# 07_ux.net
KiCad netlist of a schematic drawn in Altium Designer
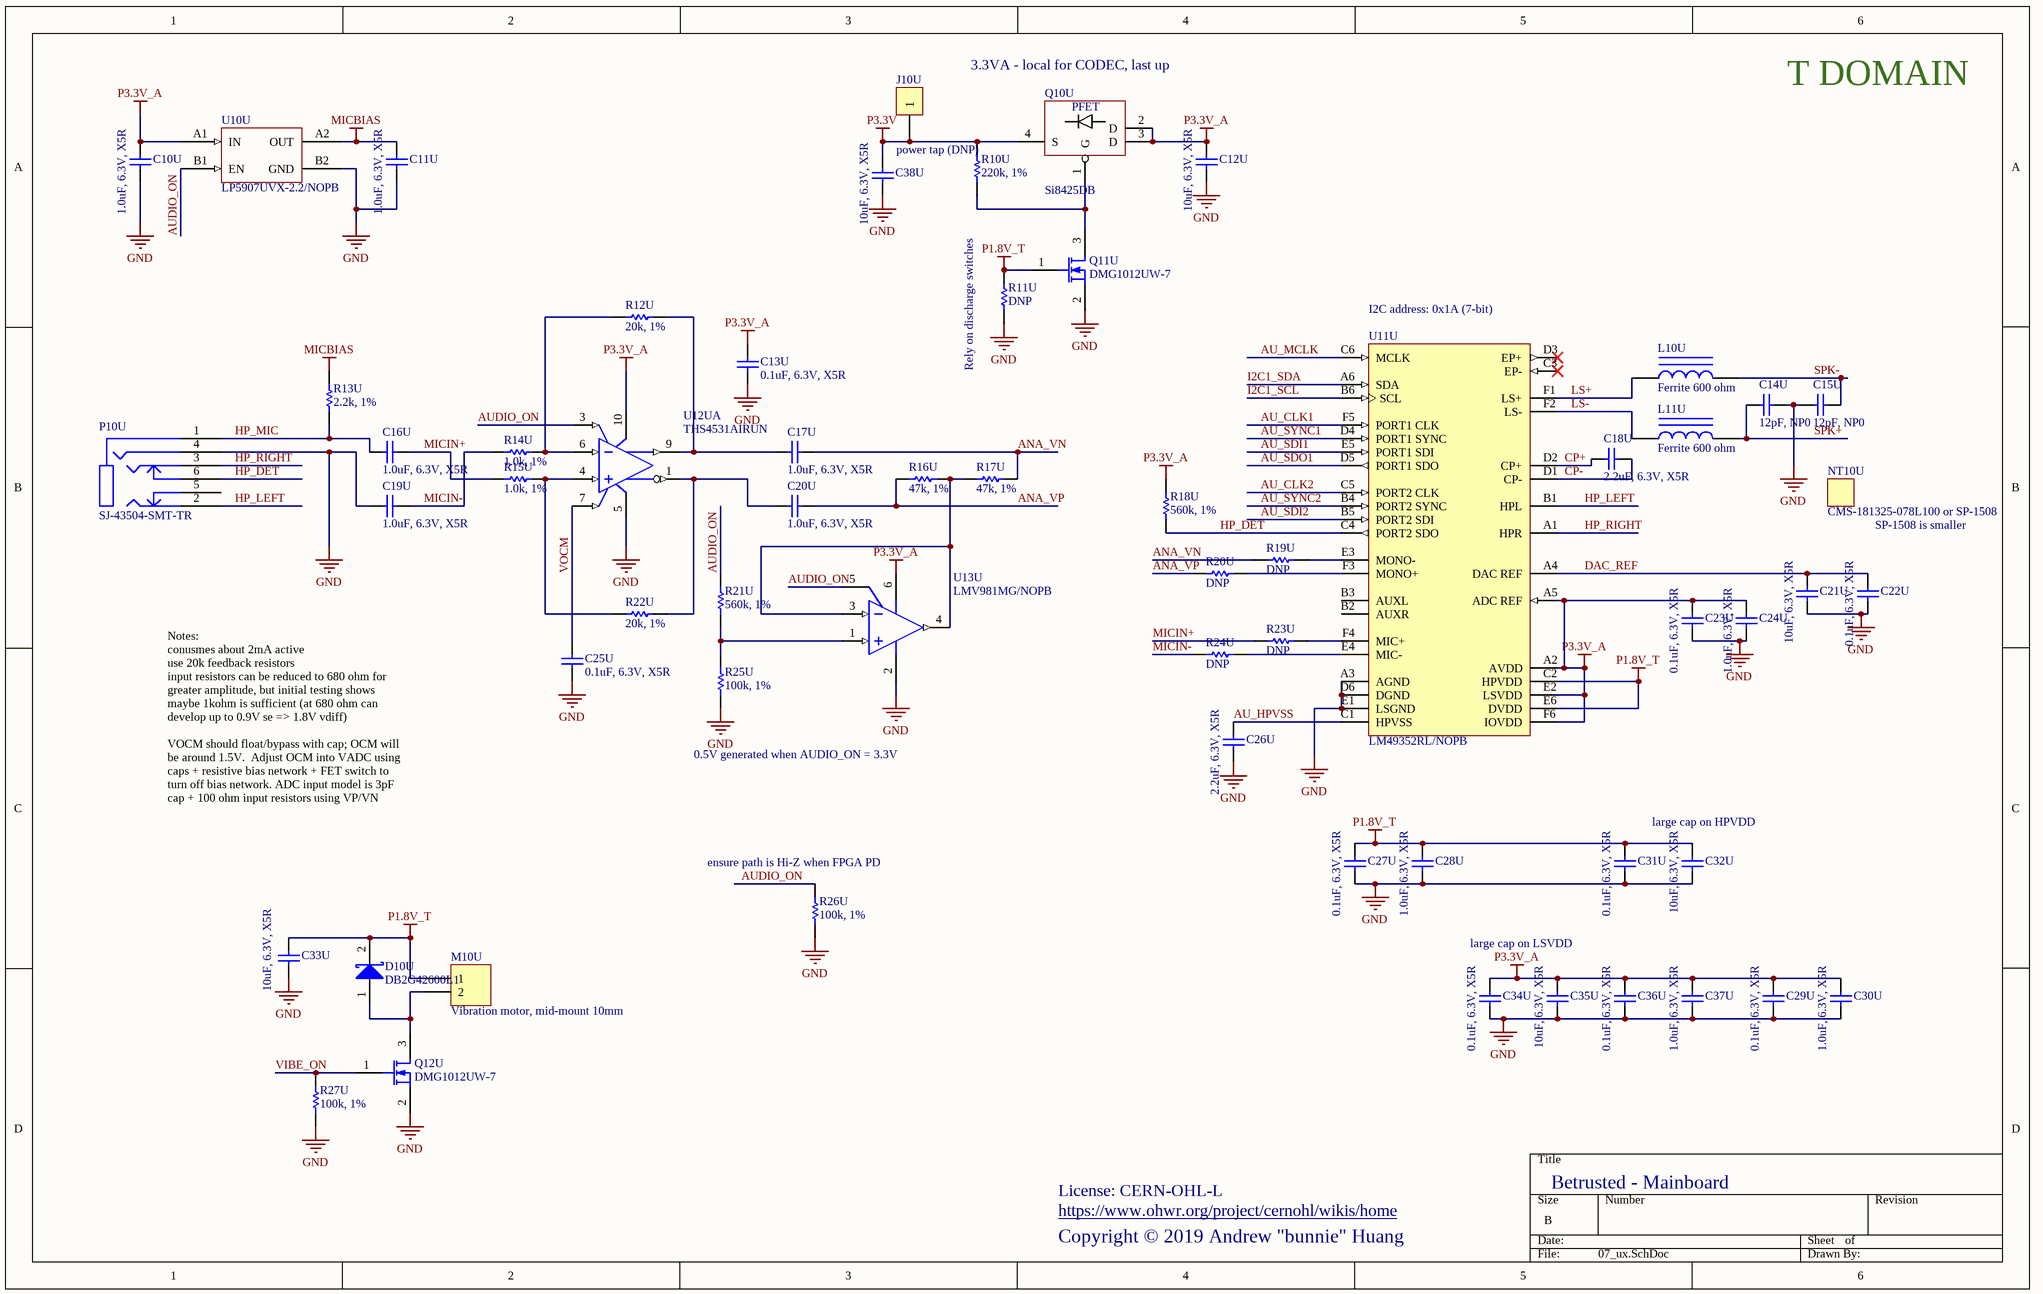
[diagram p0: 07_ux.SchDoc]

(export (version "E")
  (design (tool "Eeschema 10.0.6"))
  (components
    (comp (ref "C10U")
      (value "1.0uF, 6.3V, X5R")
      (footprint "B_CAP0201")
      (description "Capacitor (Semiconductor SIM Model)")
      (fields (field (name "MPN") "GRM033R60J105MEA2D"))
      (libsource (lib "Miscellaneous Devices") (part "Cap Semi"))
    )
    (comp (ref "C11U")
      (value "1.0uF, 6.3V, X5R")
      (footprint "B_CAP0201")
      (description "Capacitor (Semiconductor SIM Model)")
      (fields (field (name "MPN") "GRM033R60J105MEA2D"))
      (libsource (lib "Miscellaneous Devices") (part "Cap Semi"))
    )
    (comp (ref "C12U")
      (value "10uF, 6.3V, X5R")
      (footprint "B_CAP0603")
      (description "Capacitor (Semiconductor SIM Model)")
      (fields (field (name "MPN") "CL10A106MQ8NNNC"))
      (libsource (lib "Miscellaneous Devices") (part "Cap Semi"))
    )
    (comp (ref "C13U")
      (value "0.1uF, 6.3V, X5R")
      (footprint "B_CAP0201")
      (description "Capacitor (Semiconductor SIM Model)")
      (fields (field (name "MPN") "CL03A104KQ3NNNC"))
      (libsource (lib "Miscellaneous Devices") (part "Cap Semi"))
    )
    (comp (ref "C14U")
      (value "12pF, NP0")
      (footprint "B_CAP0201")
      (description "Capacitor (Semiconductor SIM Model)")
      (fields (field (name "MPN") "GRM0335C1E120JA01D"))
      (libsource (lib "Miscellaneous Devices") (part "Cap Semi"))
    )
    (comp (ref "C15U")
      (value "12pF, NP0")
      (footprint "B_CAP0201")
      (description "Capacitor (Semiconductor SIM Model)")
      (fields (field (name "MPN") "GRM0335C1E120JA01D"))
      (libsource (lib "Miscellaneous Devices") (part "Cap Semi"))
    )
    (comp (ref "C16U")
      (value "1.0uF, 6.3V, X5R")
      (footprint "B_CAP0201")
      (description "Capacitor (Semiconductor SIM Model)")
      (fields (field (name "MPN") "GRM033R60J105MEA2D"))
      (libsource (lib "Miscellaneous Devices") (part "Cap Semi"))
    )
    (comp (ref "C17U")
      (value "1.0uF, 6.3V, X5R")
      (footprint "B_CAP0201")
      (description "Capacitor (Semiconductor SIM Model)")
      (fields (field (name "MPN") "GRM033R60J105MEA2D"))
      (libsource (lib "Miscellaneous Devices") (part "Cap Semi"))
    )
    (comp (ref "C18U")
      (value "2.2uF, 6.3V, X5R")
      (footprint "B_CAP0402")
      (description "Capacitor (Semiconductor SIM Model)")
      (fields (field (name "MPN") "CL05A225MQ5NNNC"))
      (libsource (lib "Miscellaneous Devices") (part "Cap Semi"))
    )
    (comp (ref "C19U")
      (value "1.0uF, 6.3V, X5R")
      (footprint "B_CAP0201")
      (description "Capacitor (Semiconductor SIM Model)")
      (fields (field (name "MPN") "GRM033R60J105MEA2D"))
      (libsource (lib "Miscellaneous Devices") (part "Cap Semi"))
    )
    (comp (ref "C20U")
      (value "1.0uF, 6.3V, X5R")
      (footprint "B_CAP0201")
      (description "Capacitor (Semiconductor SIM Model)")
      (fields (field (name "MPN") "GRM033R60J105MEA2D"))
      (libsource (lib "Miscellaneous Devices") (part "Cap Semi"))
    )
    (comp (ref "C21U")
      (value "10uF, 6.3V, X5R")
      (footprint "B_CAP0603")
      (description "Capacitor (Semiconductor SIM Model)")
      (fields (field (name "MPN") "CL10A106MQ8NNNC"))
      (libsource (lib "Miscellaneous Devices") (part "Cap Semi"))
    )
    (comp (ref "C22U")
      (value "0.1uF, 6.3V, X5R")
      (footprint "B_CAP0201")
      (description "Capacitor (Semiconductor SIM Model)")
      (fields (field (name "MPN") "CL03A104KQ3NNNC"))
      (libsource (lib "Miscellaneous Devices") (part "Cap Semi"))
    )
    (comp (ref "C23U")
      (value "0.1uF, 6.3V, X5R")
      (footprint "B_CAP0201")
      (description "Capacitor (Semiconductor SIM Model)")
      (fields (field (name "MPN") "CL03A104KQ3NNNC"))
      (libsource (lib "Miscellaneous Devices") (part "Cap Semi"))
    )
    (comp (ref "C24U")
      (value "1.0uF, 6.3V, X5R")
      (footprint "B_CAP0201")
      (description "Capacitor (Semiconductor SIM Model)")
      (fields (field (name "MPN") "GRM033R60J105MEA2D"))
      (libsource (lib "Miscellaneous Devices") (part "Cap Semi"))
    )
    (comp (ref "C25U")
      (value "0.1uF, 6.3V, X5R")
      (footprint "B_CAP0201")
      (description "Capacitor (Semiconductor SIM Model)")
      (fields (field (name "MPN") "CL03A104KQ3NNNC"))
      (libsource (lib "Miscellaneous Devices") (part "Cap Semi"))
    )
    (comp (ref "C26U")
      (value "2.2uF, 6.3V, X5R")
      (footprint "B_CAP0402")
      (description "Capacitor (Semiconductor SIM Model)")
      (fields (field (name "MPN") "CL05A225MQ5NNNC"))
      (libsource (lib "Miscellaneous Devices") (part "Cap Semi"))
    )
    (comp (ref "C27U")
      (value "0.1uF, 6.3V, X5R")
      (footprint "B_CAP0201")
      (description "Capacitor (Semiconductor SIM Model)")
      (fields (field (name "MPN") "CL03A104KQ3NNNC"))
      (libsource (lib "Miscellaneous Devices") (part "Cap Semi"))
    )
    (comp (ref "C28U")
      (value "1.0uF, 6.3V, X5R")
      (footprint "B_CAP0201")
      (description "Capacitor (Semiconductor SIM Model)")
      (fields (field (name "MPN") "GRM033R60J105MEA2D"))
      (libsource (lib "Miscellaneous Devices") (part "Cap Semi"))
    )
    (comp (ref "C29U")
      (value "0.1uF, 6.3V, X5R")
      (footprint "B_CAP0201")
      (description "Capacitor (Semiconductor SIM Model)")
      (fields (field (name "MPN") "CL03A104KQ3NNNC"))
      (libsource (lib "Miscellaneous Devices") (part "Cap Semi"))
    )
    (comp (ref "C30U")
      (value "1.0uF, 6.3V, X5R")
      (footprint "B_CAP0201")
      (description "Capacitor (Semiconductor SIM Model)")
      (fields (field (name "MPN") "GRM033R60J105MEA2D"))
      (libsource (lib "Miscellaneous Devices") (part "Cap Semi"))
    )
    (comp (ref "C31U")
      (value "0.1uF, 6.3V, X5R")
      (footprint "B_CAP0201")
      (description "Capacitor (Semiconductor SIM Model)")
      (fields (field (name "MPN") "CL03A104KQ3NNNC"))
      (libsource (lib "Miscellaneous Devices") (part "Cap Semi"))
    )
    (comp (ref "C32U")
      (value "10uF, 6.3V, X5R")
      (footprint "B_CAP0603")
      (description "Capacitor (Semiconductor SIM Model)")
      (fields (field (name "MPN") "CL10A106MQ8NNNC"))
      (libsource (lib "Miscellaneous Devices") (part "Cap Semi"))
    )
    (comp (ref "C33U")
      (value "10uF, 6.3V, X5R")
      (footprint "B_CAP0603")
      (description "Capacitor (Semiconductor SIM Model)")
      (fields (field (name "MPN") "CL10A106MQ8NNNC"))
      (libsource (lib "Miscellaneous Devices") (part "Cap Semi"))
    )
    (comp (ref "C34U")
      (value "0.1uF, 6.3V, X5R")
      (footprint "B_CAP0201")
      (description "Capacitor (Semiconductor SIM Model)")
      (fields (field (name "MPN") "CL03A104KQ3NNNC"))
      (libsource (lib "Miscellaneous Devices") (part "Cap Semi"))
    )
    (comp (ref "C35U")
      (value "10uF, 6.3V, X5R")
      (footprint "B_CAP0603")
      (description "Capacitor (Semiconductor SIM Model)")
      (fields (field (name "MPN") "CL10A106MQ8NNNC"))
      (libsource (lib "Miscellaneous Devices") (part "Cap Semi"))
    )
    (comp (ref "C36U")
      (value "0.1uF, 6.3V, X5R")
      (footprint "B_CAP0201")
      (description "Capacitor (Semiconductor SIM Model)")
      (fields (field (name "MPN") "CL03A104KQ3NNNC"))
      (libsource (lib "Miscellaneous Devices") (part "Cap Semi"))
    )
    (comp (ref "C37U")
      (value "1.0uF, 6.3V, X5R")
      (footprint "B_CAP0201")
      (description "Capacitor (Semiconductor SIM Model)")
      (fields (field (name "MPN") "GRM033R60J105MEA2D"))
      (libsource (lib "Miscellaneous Devices") (part "Cap Semi"))
    )
    (comp (ref "C38U")
      (value "10uF, 6.3V, X5R")
      (footprint "B_CAP0603")
      (description "Capacitor (Semiconductor SIM Model)")
      (fields (field (name "MPN") "CL10A106MQ8NNNC"))
      (libsource (lib "Miscellaneous Devices") (part "Cap Semi"))
    )
    (comp (ref "D10U")
      (value "DB2G42600L1")
      (footprint "B_DIO0402")
      (description "Schottky Rectifier")
      (libsource (lib "Miscellaneous Devices") (part "Diode 11DQ03"))
    )
    (comp (ref "J10U")
      (value "power tap (DNP)")
      (footprint "RESTAP-0603")
      (description "Connector")
      (fields (field (name "MPN") "DNP"))
      (libsource (lib "*") (part "CON1"))
    )
    (comp (ref "L10U")
      (value "Ferrite 600 ohm")
      (footprint "B_IND0603")
      (description "Magnetic-Core Inductor")
      (fields (field (name "MPN") "BLM18AG601SN1D"))
      (libsource (lib "Miscellaneous Devices") (part "Inductor Iron"))
    )
    (comp (ref "L11U")
      (value "Ferrite 600 ohm")
      (footprint "B_IND0603")
      (description "Magnetic-Core Inductor")
      (fields (field (name "MPN") "BLM18AG601SN1D"))
      (libsource (lib "Miscellaneous Devices") (part "Inductor Iron"))
    )
    (comp (ref "M10U")
      (value "Vibration motor, mid-mount 10mm")
      (footprint "JINLONG-C1020K001F")
      (fields (field (name "MPN") "C1020K001F") (field (name "PUBLISHER") "Altium Limited"))
      (libsource (lib "Miscellaneous Connectors") (part "Header 2"))
    )
    (comp (ref "NT10U")
      (value "CMS-181325-078L100 or SP-1508")
      (description "Placeholder for non-board BOM items")
      (libsource (lib "commonsch") (part "NOTE"))
    )
    (comp (ref "P10U")
      (value "SJ-43504-SMT-TR")
      (footprint "CUI_SJ_43504_SMT_TR_FLIP")
      (description "Mid mount audio jack")
      (libsource (lib "commonsch-new") (part "CUI_3.5MM_STEREO_MIC"))
    )
    (comp (ref "Q10U")
      (value "Si8425DB")
      (footprint "VISHAY_MICRO_FOOT_4_BUMP")
      (description "P-channel 20V 6.2A 27mOhm @ -2.5V")
      (fields (field (name "MPN") "SI8457DB-T1-E1"))
      (libsource (lib "temp-to-merge") (part "Si8425DB"))
    )
    (comp (ref "Q11U")
      (value "DMG1012UW-7")
      (footprint "SOT323-3AN")
      (description "N-Channel MOSFET")
      (fields (field (name "PUBLISHER") "Altium Limited"))
      (libsource (lib "Miscellaneous Devices") (part "MOSFET-N"))
    )
    (comp (ref "Q12U")
      (value "DMG1012UW-7")
      (footprint "SOT323-3AN")
      (description "N-Channel MOSFET")
      (fields (field (name "PUBLISHER") "Altium Limited"))
      (libsource (lib "Miscellaneous Devices") (part "MOSFET-N"))
    )
    (comp (ref "R10U")
      (value "220k, 1%")
      (footprint "B_RES0201")
      (description "Resistor")
      (fields (field (name "MPN") "ANY"))
      (libsource (lib "Miscellaneous Devices") (part "Res1"))
    )
    (comp (ref "R11U")
      (value "DNP")
      (footprint "B_RES0201")
      (description "Resistor")
      (fields (field (name "MPN") "ANY"))
      (libsource (lib "Miscellaneous Devices") (part "Res1"))
    )
    (comp (ref "R12U")
      (value "20k, 1%")
      (footprint "B_RES0201")
      (description "Resistor")
      (fields (field (name "MPN") "ANY"))
      (libsource (lib "Miscellaneous Devices") (part "Res1"))
    )
    (comp (ref "R13U")
      (value "2.2k, 1%")
      (footprint "B_RES0201")
      (description "Resistor")
      (fields (field (name "MPN") "ANY"))
      (libsource (lib "Miscellaneous Devices") (part "Res1"))
    )
    (comp (ref "R14U")
      (value "1.0k, 1%")
      (footprint "B_RES0201")
      (description "Resistor")
      (fields (field (name "MPN") "ANY"))
      (libsource (lib "Miscellaneous Devices") (part "Res1"))
    )
    (comp (ref "R15U")
      (value "1.0k, 1%")
      (footprint "B_RES0201")
      (description "Resistor")
      (fields (field (name "MPN") "ANY"))
      (libsource (lib "Miscellaneous Devices") (part "Res1"))
    )
    (comp (ref "R16U")
      (value "47k, 1%")
      (footprint "B_RES0201")
      (description "Resistor")
      (fields (field (name "MPN") "ANY"))
      (libsource (lib "Miscellaneous Devices") (part "Res1"))
    )
    (comp (ref "R17U")
      (value "47k, 1%")
      (footprint "B_RES0201")
      (description "Resistor")
      (fields (field (name "MPN") "ANY"))
      (libsource (lib "Miscellaneous Devices") (part "Res1"))
    )
    (comp (ref "R18U")
      (value "560k, 1%")
      (footprint "B_RES0201")
      (description "Resistor")
      (fields (field (name "MPN") "ANY"))
      (libsource (lib "Miscellaneous Devices") (part "Res1"))
    )
    (comp (ref "R19U")
      (value "DNP")
      (footprint "B_RES0201")
      (description "Resistor")
      (fields (field (name "MPN") "ANY"))
      (libsource (lib "Miscellaneous Devices") (part "Res1"))
    )
    (comp (ref "R20U")
      (value "DNP")
      (footprint "B_RES0201")
      (description "Resistor")
      (fields (field (name "MPN") "ANY"))
      (libsource (lib "Miscellaneous Devices") (part "Res1"))
    )
    (comp (ref "R21U")
      (value "560k, 1%")
      (footprint "B_RES0201")
      (description "Resistor")
      (fields (field (name "MPN") "ANY"))
      (libsource (lib "Miscellaneous Devices") (part "Res1"))
    )
    (comp (ref "R22U")
      (value "20k, 1%")
      (footprint "B_RES0201")
      (description "Resistor")
      (fields (field (name "MPN") "ANY"))
      (libsource (lib "Miscellaneous Devices") (part "Res1"))
    )
    (comp (ref "R23U")
      (value "DNP")
      (footprint "B_RES0201")
      (description "Resistor")
      (fields (field (name "MPN") "ANY"))
      (libsource (lib "Miscellaneous Devices") (part "Res1"))
    )
    (comp (ref "R24U")
      (value "DNP")
      (footprint "B_RES0201")
      (description "Resistor")
      (fields (field (name "MPN") "ANY"))
      (libsource (lib "Miscellaneous Devices") (part "Res1"))
    )
    (comp (ref "R25U")
      (value "100k, 1%")
      (footprint "B_RES0201")
      (description "Resistor")
      (fields (field (name "MPN") "ANY"))
      (libsource (lib "Miscellaneous Devices") (part "Res1"))
    )
    (comp (ref "R26U")
      (value "100k, 1%")
      (footprint "B_RES0201")
      (description "Resistor")
      (fields (field (name "MPN") "ANY"))
      (libsource (lib "Miscellaneous Devices") (part "Res1"))
    )
    (comp (ref "R27U")
      (value "100k, 1%")
      (footprint "B_RES0201")
      (description "Resistor")
      (fields (field (name "MPN") "ANY"))
      (libsource (lib "Miscellaneous Devices") (part "Res1"))
    )
    (comp (ref "U10U")
      (value "LP5907UVX-2.2/NOPB")
      (footprint "TI_YKE004")
      (description "Ultra low-noise 250mA LDO for RF and analog in DSBGA")
      (libsource (lib "commonsch-new") (part "LP5907UVX"))
    )
    (comp (ref "U11U")
      (value "LM49352RL/NOPB")
      (footprint "YPG0036AWAW")
      (libsource (lib "Copy of AMP-AUDA-LM49352-36-bunnie") (part "AMP-AUDA-LM49352-36"))
    )
    (comp (ref "U12U")
      (value "THS4531AIRUN")
      (footprint "RUN0010A")
      (description "Ultra Low-Power, RRIO, Fully Differential Amplifier")
      (fields (field (name "MPN") "THS4531AIRUNT"))
      (libsource (lib "TI-THS4531X-RUN10") (part "TI-THS4531X-RUN10"))
    )
    (comp (ref "U13U")
      (value "LMV981MG/NOPB")
      (footprint "DCK0006A_N")
      (description "Single 1.8V, RRIO Operational Amplifiers with Shutdown, 6-pin SC-70, Pb-Free")
      (libsource (lib "Altium Content Vault") (part "AMP-OPA-LMV981-6"))
    )
  )
  (nets
    (net (code "1") (name "/ANA_VN") (class "Default")
      (node (ref "C17U") (pin "2") (pinfunction "2_2") (pintype "passive"))
      (node (ref "R17U") (pin "1") (pinfunction "1_1") (pintype "passive"))
      (node (ref "R19U") (pin "2") (pinfunction "2_2") (pintype "passive"))
    )
    (net (code "2") (name "/ANA_VP") (class "Default")
      (node (ref "C20U") (pin "2") (pinfunction "2_2") (pintype "passive"))
      (node (ref "R16U") (pin "2") (pinfunction "2_2") (pintype "passive"))
      (node (ref "R20U") (pin "2") (pinfunction "2_2") (pintype "passive"))
    )
    (net (code "3") (name "/AUDIO_ON") (class "Default")
      (node (ref "R21U") (pin "2") (pinfunction "2_2") (pintype "passive"))
      (node (ref "R26U") (pin "2") (pinfunction "2_2") (pintype "passive"))
      (node (ref "U10U") (pin "B1") (pinfunction "EN_B1") (pintype "input"))
      (node (ref "U12U") (pin "3") (pinfunction "~{PD}_3") (pintype "input"))
      (node (ref "U13U") (pin "5") (pinfunction "~{SHDN}_5") (pintype "passive"))
    )
    (net (code "4") (name "/AU_CLK1") (class "Default")
      (node (ref "U11U") (pin "F5") (pinfunction "PORT1_CLK_F5") (pintype "input"))
    )
    (net (code "5") (name "/AU_CLK2") (class "Default")
      (node (ref "U11U") (pin "C5") (pinfunction "PORT2_CLK_C5") (pintype "input"))
    )
    (net (code "6") (name "/AU_HPVSS") (class "Default")
      (node (ref "C26U") (pin "2") (pinfunction "2_2") (pintype "passive"))
      (node (ref "U11U") (pin "C1") (pinfunction "HPVSS_C1") (pintype "power_in"))
    )
    (net (code "7") (name "/AU_MCLK") (class "Default")
      (node (ref "U11U") (pin "C6") (pinfunction "MCLK_C6") (pintype "input"))
    )
    (net (code "8") (name "/AU_SDI1") (class "Default")
      (node (ref "U11U") (pin "E5") (pinfunction "PORT1_SDI_E5") (pintype "input"))
    )
    (net (code "9") (name "/AU_SDI2") (class "Default")
      (node (ref "U11U") (pin "B5") (pinfunction "PORT2_SDI_B5") (pintype "input"))
    )
    (net (code "10") (name "/AU_SDO1") (class "Default")
      (node (ref "U11U") (pin "D5") (pinfunction "PORT1_SDO_D5") (pintype "output"))
    )
    (net (code "11") (name "/AU_SYNC1") (class "Default")
      (node (ref "U11U") (pin "D4") (pinfunction "PORT1_SYNC_D4") (pintype "input"))
    )
    (net (code "12") (name "/AU_SYNC2") (class "Default")
      (node (ref "U11U") (pin "B4") (pinfunction "PORT2_SYNC_B4") (pintype "input"))
    )
    (net (code "13") (name "/CP+") (class "Default")
      (node (ref "C18U") (pin "2") (pinfunction "2_2") (pintype "passive"))
      (node (ref "U11U") (pin "D2") (pinfunction "CP+_D2") (pintype "passive"))
    )
    (net (code "14") (name "/CP-") (class "Default")
      (node (ref "C18U") (pin "1") (pinfunction "1_1") (pintype "passive"))
      (node (ref "U11U") (pin "D1") (pinfunction "CP-_D1") (pintype "passive"))
    )
    (net (code "15") (name "/DAC_REF") (class "Default")
      (node (ref "C21U") (pin "1") (pinfunction "1_1") (pintype "passive"))
      (node (ref "C22U") (pin "1") (pinfunction "1_1") (pintype "passive"))
      (node (ref "U11U") (pin "A4") (pinfunction "DAC_REF_A4") (pintype "power_in"))
    )
    (net (code "16") (name "/HP_DET") (class "Default")
      (node (ref "P10U") (pin "6") (pinfunction "RING1_SW_6") (pintype "passive"))
      (node (ref "R18U") (pin "1") (pinfunction "1_1") (pintype "passive"))
      (node (ref "U11U") (pin "C4") (pinfunction "PORT2_SDO_C4") (pintype "output"))
    )
    (net (code "17") (name "/HP_LEFT") (class "Default")
      (node (ref "P10U") (pin "2") (pinfunction "TIP_2") (pintype "passive"))
      (node (ref "U11U") (pin "B1") (pinfunction "HPL_B1") (pintype "passive"))
    )
    (net (code "18") (name "/HP_MIC") (class "Default")
      (node (ref "C16U") (pin "1") (pinfunction "1_1") (pintype "passive"))
      (node (ref "P10U") (pin "1") (pinfunction "SLEEVE_1") (pintype "passive"))
      (node (ref "R13U") (pin "1") (pinfunction "1_1") (pintype "passive"))
    )
    (net (code "19") (name "/HP_RIGHT") (class "Default")
      (node (ref "P10U") (pin "3") (pinfunction "RING1_3") (pintype "passive"))
      (node (ref "U11U") (pin "A1") (pinfunction "HPR_A1") (pintype "passive"))
    )
    (net (code "20") (name "/I2C1_SCL") (class "Default")
      (node (ref "U11U") (pin "B6") (pinfunction "SCL_B6") (pintype "input"))
    )
    (net (code "21") (name "/I2C1_SDA") (class "Default")
      (node (ref "U11U") (pin "A6") (pinfunction "SDA_A6") (pintype "input"))
    )
    (net (code "22") (name "/LS+") (class "Default")
      (node (ref "L10U") (pin "1") (pinfunction "1_1") (pintype "passive"))
      (node (ref "U11U") (pin "F1") (pinfunction "LS+_F1") (pintype "power_in"))
    )
    (net (code "23") (name "/LS-") (class "Default")
      (node (ref "L11U") (pin "1") (pinfunction "1_1") (pintype "passive"))
      (node (ref "U11U") (pin "F2") (pinfunction "LS-_F2") (pintype "power_in"))
    )
    (net (code "24") (name "/MICIN+") (class "Default")
      (node (ref "C16U") (pin "2") (pinfunction "2_2") (pintype "passive"))
      (node (ref "R15U") (pin "2") (pinfunction "2_2") (pintype "passive"))
      (node (ref "R23U") (pin "2") (pinfunction "2_2") (pintype "passive"))
    )
    (net (code "25") (name "/MICIN-") (class "Default")
      (node (ref "C19U") (pin "2") (pinfunction "2_2") (pintype "passive"))
      (node (ref "R14U") (pin "2") (pinfunction "2_2") (pintype "passive"))
      (node (ref "R24U") (pin "2") (pinfunction "2_2") (pintype "passive"))
    )
    (net (code "26") (name "/SPK+") (class "Default")
      (node (ref "C14U") (pin "1") (pinfunction "1_1") (pintype "passive"))
      (node (ref "L11U") (pin "2") (pinfunction "2_2") (pintype "passive"))
    )
    (net (code "27") (name "/SPK-") (class "Default")
      (node (ref "C15U") (pin "2") (pinfunction "2_2") (pintype "passive"))
      (node (ref "L10U") (pin "2") (pinfunction "2_2") (pintype "passive"))
    )
    (net (code "28") (name "/VIBE_ON") (class "Default")
      (node (ref "Q12U") (pin "1") (pinfunction "G_1") (pintype "passive"))
      (node (ref "R27U") (pin "2") (pinfunction "2_2") (pintype "passive"))
    )
    (net (code "29") (name "/VOCM") (class "Default")
      (node (ref "C25U") (pin "2") (pinfunction "2_2") (pintype "passive"))
      (node (ref "U12U") (pin "7") (pinfunction "VOCM_7") (pintype "input"))
    )
    (net (code "30") (name "GND") (class "Default")
      (node (ref "C10U") (pin "2") (pinfunction "2_2") (pintype "passive"))
      (node (ref "C11U") (pin "2") (pinfunction "2_2") (pintype "passive"))
      (node (ref "C12U") (pin "2") (pinfunction "2_2") (pintype "passive"))
      (node (ref "C13U") (pin "1") (pinfunction "1_1") (pintype "passive"))
      (node (ref "C14U") (pin "2") (pinfunction "2_2") (pintype "passive"))
      (node (ref "C15U") (pin "1") (pinfunction "1_1") (pintype "passive"))
      (node (ref "C19U") (pin "1") (pinfunction "1_1") (pintype "passive"))
      (node (ref "C21U") (pin "2") (pinfunction "2_2") (pintype "passive"))
      (node (ref "C22U") (pin "2") (pinfunction "2_2") (pintype "passive"))
      (node (ref "C23U") (pin "2") (pinfunction "2_2") (pintype "passive"))
      (node (ref "C24U") (pin "1") (pinfunction "1_1") (pintype "passive"))
      (node (ref "C25U") (pin "1") (pinfunction "1_1") (pintype "passive"))
      (node (ref "C26U") (pin "1") (pinfunction "1_1") (pintype "passive"))
      (node (ref "C27U") (pin "2") (pinfunction "2_2") (pintype "passive"))
      (node (ref "C28U") (pin "1") (pinfunction "1_1") (pintype "passive"))
      (node (ref "C29U") (pin "2") (pinfunction "2_2") (pintype "passive"))
      (node (ref "C30U") (pin "1") (pinfunction "1_1") (pintype "passive"))
      (node (ref "C31U") (pin "2") (pinfunction "2_2") (pintype "passive"))
      (node (ref "C32U") (pin "2") (pinfunction "2_2") (pintype "passive"))
      (node (ref "C33U") (pin "1") (pinfunction "1_1") (pintype "passive"))
      (node (ref "C34U") (pin "2") (pinfunction "2_2") (pintype "passive"))
      (node (ref "C35U") (pin "2") (pinfunction "2_2") (pintype "passive"))
      (node (ref "C36U") (pin "2") (pinfunction "2_2") (pintype "passive"))
      (node (ref "C37U") (pin "1") (pinfunction "1_1") (pintype "passive"))
      (node (ref "C38U") (pin "2") (pinfunction "2_2") (pintype "passive"))
      (node (ref "P10U") (pin "4") (pinfunction "RING2_4") (pintype "passive"))
      (node (ref "Q11U") (pin "2") (pinfunction "S_2") (pintype "passive"))
      (node (ref "Q12U") (pin "2") (pinfunction "S_2") (pintype "passive"))
      (node (ref "R11U") (pin "1") (pinfunction "1_1") (pintype "passive"))
      (node (ref "R25U") (pin "1") (pinfunction "1_1") (pintype "passive"))
      (node (ref "R26U") (pin "1") (pinfunction "1_1") (pintype "passive"))
      (node (ref "R27U") (pin "1") (pinfunction "1_1") (pintype "passive"))
      (node (ref "U10U") (pin "B2") (pinfunction "GND_B2") (pintype "power_in"))
      (node (ref "U11U") (pin "A3") (pinfunction "AGND_A3") (pintype "power_in"))
      (node (ref "U11U") (pin "D6") (pinfunction "DGND_D6") (pintype "power_in"))
      (node (ref "U11U") (pin "E1") (pinfunction "LSGND_E1") (pintype "power_in"))
      (node (ref "U12U") (pin "5") (pinfunction "VS-_5") (pintype "power_in"))
      (node (ref "U13U") (pin "2") (pinfunction "GND_2") (pintype "power_in"))
    )
    (net (code "31") (name "MICBIAS") (class "Default")
      (node (ref "C11U") (pin "1") (pinfunction "1_1") (pintype "passive"))
      (node (ref "R13U") (pin "2") (pinfunction "2_2") (pintype "passive"))
      (node (ref "U10U") (pin "A2") (pinfunction "OUT_A2") (pintype "power_in"))
    )
    (net (code "32") (name "Net-(D10U-A)") (class "Default")
      (node (ref "D10U") (pin "1") (pinfunction "A_1") (pintype "passive"))
      (node (ref "M10U") (pin "2") (pinfunction "2_2") (pintype "passive"))
      (node (ref "Q12U") (pin "3") (pinfunction "D_3") (pintype "passive"))
    )
    (net (code "33") (name "Net-(Q10U-G)") (class "Default")
      (node (ref "Q10U") (pin "1") (pinfunction "G_1") (pintype "passive"))
      (node (ref "Q11U") (pin "3") (pinfunction "D_3") (pintype "passive"))
      (node (ref "R10U") (pin "1") (pinfunction "1_1") (pintype "passive"))
    )
    (net (code "34") (name "Net-(U11U-MIC+)") (class "Default")
      (node (ref "R23U") (pin "1") (pinfunction "1_1") (pintype "passive"))
      (node (ref "U11U") (pin "F4") (pinfunction "MIC+_F4") (pintype "passive"))
    )
    (net (code "35") (name "Net-(U11U-MIC-)") (class "Default")
      (node (ref "R24U") (pin "1") (pinfunction "1_1") (pintype "passive"))
      (node (ref "U11U") (pin "E4") (pinfunction "MIC-_E4") (pintype "passive"))
    )
    (net (code "36") (name "Net-(U11U-MONO+)") (class "Default")
      (node (ref "R20U") (pin "1") (pinfunction "1_1") (pintype "passive"))
      (node (ref "U11U") (pin "F3") (pinfunction "MONO+_F3") (pintype "passive"))
    )
    (net (code "37") (name "Net-(U11U-MONO-)") (class "Default")
      (node (ref "R19U") (pin "1") (pinfunction "1_1") (pintype "passive"))
      (node (ref "U11U") (pin "E3") (pinfunction "MONO-_E3") (pintype "passive"))
    )
    (net (code "38") (name "Net-(U12UA-VIN+)") (class "Default")
      (node (ref "R15U") (pin "1") (pinfunction "1_1") (pintype "passive"))
      (node (ref "R22U") (pin "2") (pinfunction "2_2") (pintype "passive"))
      (node (ref "U12U") (pin "4") (pinfunction "VIN+_4") (pintype "input"))
    )
    (net (code "39") (name "Net-(U12UA-VIN-)") (class "Default")
      (node (ref "R12U") (pin "2") (pinfunction "2_2") (pintype "passive"))
      (node (ref "R14U") (pin "1") (pinfunction "1_1") (pintype "passive"))
      (node (ref "U12U") (pin "6") (pinfunction "VIN-_6") (pintype "input"))
    )
    (net (code "40") (name "Net-(U12UA-VOUT+)") (class "Default")
      (node (ref "C17U") (pin "1") (pinfunction "1_1") (pintype "passive"))
      (node (ref "R12U") (pin "1") (pinfunction "1_1") (pintype "passive"))
      (node (ref "U12U") (pin "9") (pinfunction "VOUT+_9") (pintype "output"))
    )
    (net (code "41") (name "Net-(U12UA-VOUT-)") (class "Default")
      (node (ref "C20U") (pin "1") (pinfunction "1_1") (pintype "passive"))
      (node (ref "R22U") (pin "1") (pinfunction "1_1") (pintype "passive"))
      (node (ref "U12U") (pin "1") (pinfunction "VOUT-_1") (pintype "output"))
    )
    (net (code "42") (name "Net-(U13U-IN+)") (class "Default")
      (node (ref "R21U") (pin "1") (pinfunction "1_1") (pintype "passive"))
      (node (ref "R25U") (pin "2") (pinfunction "2_2") (pintype "passive"))
      (node (ref "U13U") (pin "1") (pinfunction "IN+_1") (pintype "input"))
    )
    (net (code "43") (name "Net-(U13U-IN-)") (class "Default")
      (node (ref "R16U") (pin "1") (pinfunction "1_1") (pintype "passive"))
      (node (ref "R17U") (pin "2") (pinfunction "2_2") (pintype "passive"))
      (node (ref "U13U") (pin "3") (pinfunction "IN-_3") (pintype "input"))
      (node (ref "U13U") (pin "4") (pinfunction "OUT_4") (pintype "output"))
    )
    (net (code "44") (name "P1.8V_T") (class "Default")
      (node (ref "C27U") (pin "1") (pinfunction "1_1") (pintype "passive"))
      (node (ref "C28U") (pin "2") (pinfunction "2_2") (pintype "passive"))
      (node (ref "C31U") (pin "1") (pinfunction "1_1") (pintype "passive"))
      (node (ref "C32U") (pin "1") (pinfunction "1_1") (pintype "passive"))
      (node (ref "C33U") (pin "2") (pinfunction "2_2") (pintype "passive"))
      (node (ref "D10U") (pin "2") (pinfunction "K_2") (pintype "passive"))
      (node (ref "M10U") (pin "1") (pinfunction "1_1") (pintype "passive"))
      (node (ref "Q11U") (pin "1") (pinfunction "G_1") (pintype "passive"))
      (node (ref "R11U") (pin "2") (pinfunction "2_2") (pintype "passive"))
      (node (ref "U11U") (pin "C2") (pinfunction "HPVDD_C2") (pintype "power_in"))
      (node (ref "U11U") (pin "E6") (pinfunction "DVDD_E6") (pintype "power_in"))
    )
    (net (code "45") (name "P3.3V") (class "Default")
      (node (ref "C38U") (pin "1") (pinfunction "1_1") (pintype "passive"))
      (node (ref "J10U") (pin "1") (pinfunction "1_1") (pintype "passive"))
      (node (ref "Q10U") (pin "4") (pinfunction "S_4") (pintype "passive"))
      (node (ref "R10U") (pin "2") (pinfunction "2_2") (pintype "passive"))
    )
    (net (code "46") (name "P3.3V_A") (class "Default")
      (node (ref "C10U") (pin "1") (pinfunction "1_1") (pintype "passive"))
      (node (ref "C12U") (pin "1") (pinfunction "1_1") (pintype "passive"))
      (node (ref "C13U") (pin "2") (pinfunction "2_2") (pintype "passive"))
      (node (ref "C23U") (pin "1") (pinfunction "1_1") (pintype "passive"))
      (node (ref "C24U") (pin "2") (pinfunction "2_2") (pintype "passive"))
      (node (ref "C29U") (pin "1") (pinfunction "1_1") (pintype "passive"))
      (node (ref "C30U") (pin "2") (pinfunction "2_2") (pintype "passive"))
      (node (ref "C34U") (pin "1") (pinfunction "1_1") (pintype "passive"))
      (node (ref "C35U") (pin "1") (pinfunction "1_1") (pintype "passive"))
      (node (ref "C36U") (pin "1") (pinfunction "1_1") (pintype "passive"))
      (node (ref "C37U") (pin "2") (pinfunction "2_2") (pintype "passive"))
      (node (ref "Q10U") (pin "2") (pinfunction "D_2") (pintype "passive"))
      (node (ref "Q10U") (pin "3") (pinfunction "D_3") (pintype "passive"))
      (node (ref "R18U") (pin "2") (pinfunction "2_2") (pintype "passive"))
      (node (ref "U10U") (pin "A1") (pinfunction "IN_A1") (pintype "input"))
      (node (ref "U11U") (pin "A2") (pinfunction "AVDD_A2") (pintype "power_in"))
      (node (ref "U11U") (pin "A5") (pinfunction "ADC_REF_A5") (pintype "input"))
      (node (ref "U11U") (pin "E2") (pinfunction "LSVDD_E2") (pintype "power_in"))
      (node (ref "U11U") (pin "F6") (pinfunction "IOVDD_F6") (pintype "power_in"))
      (node (ref "U12U") (pin "10") (pinfunction "VS+_10") (pintype "power_in"))
      (node (ref "U13U") (pin "6") (pinfunction "VDD_6") (pintype "power_in"))
    )
    (net (code "47") (name "unconnected-(P10U-TIP_SW-Pad5)") (class "Default")
      (node (ref "P10U") (pin "5") (pinfunction "TIP_SW_5") (pintype "passive"))
    )
    (net (code "48") (name "unconnected-(U11U-AUXL-PadB3)") (class "Default")
      (node (ref "U11U") (pin "B3") (pinfunction "AUXL_B3") (pintype "passive"))
    )
    (net (code "49") (name "unconnected-(U11U-AUXR-PadB2)") (class "Default")
      (node (ref "U11U") (pin "B2") (pinfunction "AUXR_B2") (pintype "passive"))
    )
    (net (code "50") (name "unconnected-(U11U-EP+-PadD3)") (class "Default")
      (node (ref "U11U") (pin "D3") (pinfunction "EP+_D3") (pintype "output+no_connect"))
    )
    (net (code "51") (name "unconnected-(U11U-EP--PadC3)") (class "Default")
      (node (ref "U11U") (pin "C3") (pinfunction "EP-_C3") (pintype "input+no_connect"))
    )
  )
)
